# CH335fUSBHub_250914_A.net
KiCad netlist of a schematic drawn in EasyEDA Pro
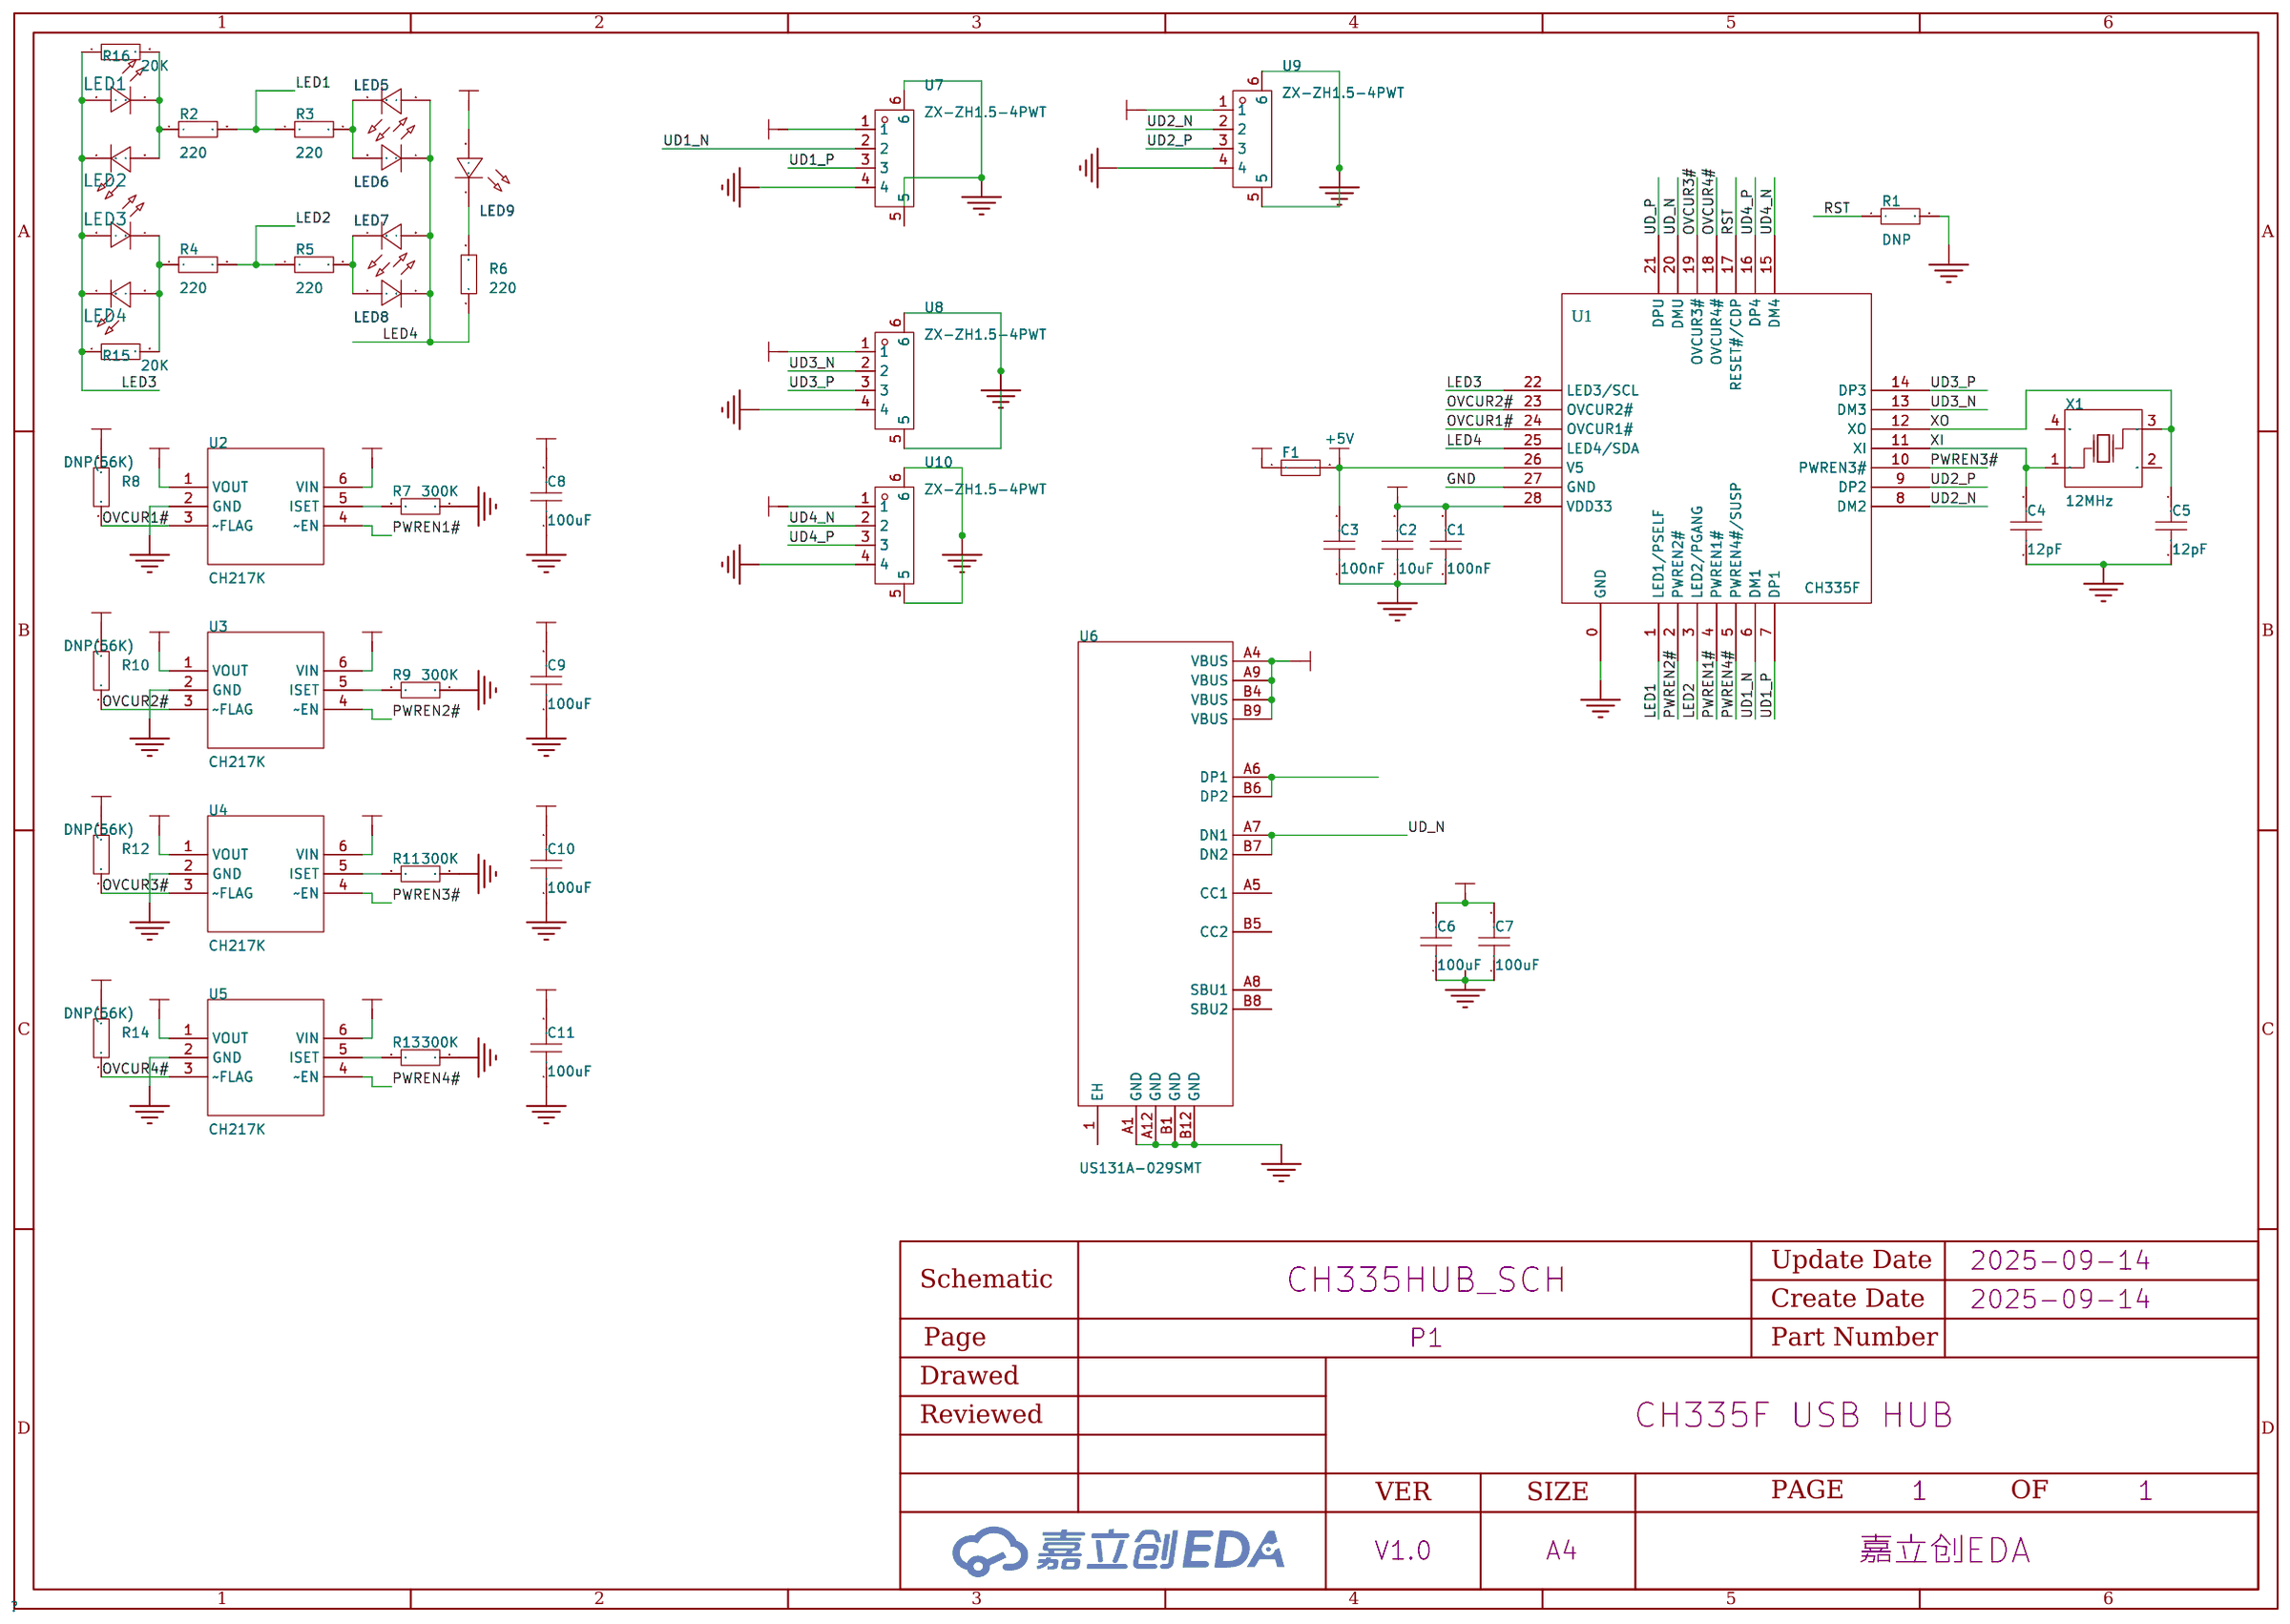
[diagram p0: schematic sheet]

(export (version "E")
  (design (tool "Eeschema 10.0.6"))
  (components
    (comp (ref "C1")
      (value "100nF")
      (footprint "easyedapro:C0805")
      (libsource (lib "easyedapro") (part "CapAcitance"))
    )
    (comp (ref "C2")
      (value "10uF")
      (footprint "easyedapro:C0805")
      (libsource (lib "easyedapro") (part "CapAcitance"))
    )
    (comp (ref "C3")
      (value "100nF")
      (footprint "easyedapro:C0805")
      (libsource (lib "easyedapro") (part "CapAcitance"))
    )
    (comp (ref "C4")
      (value "12pF")
      (footprint "easyedapro:C0805")
      (libsource (lib "easyedapro") (part "CapAcitance"))
    )
    (comp (ref "C5")
      (value "12pF")
      (footprint "easyedapro:C0805")
      (libsource (lib "easyedapro") (part "CapAcitance"))
    )
    (comp (ref "C6")
      (value "100uF")
      (footprint "easyedapro:C0805")
      (libsource (lib "easyedapro") (part "CapAcitance"))
    )
    (comp (ref "C7")
      (value "100uF")
      (footprint "easyedapro:C0805")
      (libsource (lib "easyedapro") (part "CapAcitance"))
    )
    (comp (ref "C8")
      (value "100uF")
      (footprint "easyedapro:C0805")
      (libsource (lib "easyedapro") (part "CapAcitance"))
    )
    (comp (ref "C9")
      (value "100uF")
      (footprint "easyedapro:C0805")
      (libsource (lib "easyedapro") (part "CapAcitance"))
    )
    (comp (ref "C10")
      (value "100uF")
      (footprint "easyedapro:C0805")
      (libsource (lib "easyedapro") (part "CapAcitance"))
    )
    (comp (ref "C11")
      (value "100uF")
      (footprint "easyedapro:C0805")
      (libsource (lib "easyedapro") (part "CapAcitance"))
    )
    (comp (ref "F1")
      (value "SMD0805B050TF")
      (footprint "easyedapro:F0805")
      (description "最大电压:6V;最大电流:100A;保持电流:500mA;跳闸电流:1A;")
      (fields (field (name "Manufacturer") "Brightking(君耀电子)"))
      (libsource (lib "easyedapro") (part "SMD0805B050TF"))
    )
    (comp (ref "LED1")
      (value "~")
      (footprint "easyedapro:LED_0805")
      (libsource (lib "easyedapro") (part "LED_R"))
    )
    (comp (ref "LED2")
      (value "~")
      (footprint "easyedapro:LED_0805")
      (libsource (lib "easyedapro") (part "LED_R"))
    )
    (comp (ref "LED3")
      (value "~")
      (footprint "easyedapro:LED_0805")
      (libsource (lib "easyedapro") (part "LED_R"))
    )
    (comp (ref "LED4")
      (value "~")
      (footprint "easyedapro:LED_0805")
      (libsource (lib "easyedapro") (part "LED_R"))
    )
    (comp (ref "LED5")
      (value "~")
      (footprint "easyedapro:LED_0805")
      (libsource (lib "easyedapro") (part "LED_G"))
    )
    (comp (ref "LED6")
      (value "~")
      (footprint "easyedapro:LED_0805")
      (libsource (lib "easyedapro") (part "LED_G"))
    )
    (comp (ref "LED7")
      (value "~")
      (footprint "easyedapro:LED_0805")
      (libsource (lib "easyedapro") (part "LED_G"))
    )
    (comp (ref "LED8")
      (value "~")
      (footprint "easyedapro:LED_0805")
      (libsource (lib "easyedapro") (part "LED_G"))
    )
    (comp (ref "LED9")
      (value "~")
      (footprint "easyedapro:LED_0805")
      (libsource (lib "easyedapro") (part "LED_G"))
    )
    (comp (ref "R1") (value "DNP") (footprint "easyedapro:R0805") (libsource (lib "easyedapro") (part "电阻")))
    (comp (ref "R2") (value "220") (footprint "easyedapro:R0805") (libsource (lib "easyedapro") (part "电阻")))
    (comp (ref "R3") (value "220") (footprint "easyedapro:R0805") (libsource (lib "easyedapro") (part "电阻")))
    (comp (ref "R4") (value "220") (footprint "easyedapro:R0805") (libsource (lib "easyedapro") (part "电阻")))
    (comp (ref "R5") (value "220") (footprint "easyedapro:R0805") (libsource (lib "easyedapro") (part "电阻")))
    (comp (ref "R6") (value "220") (footprint "easyedapro:R0805") (libsource (lib "easyedapro") (part "电阻")))
    (comp (ref "R7") (value "300K") (footprint "easyedapro:R0805") (libsource (lib "easyedapro") (part "电阻")))
    (comp (ref "R8")
      (value "DNP(56K)")
      (footprint "easyedapro:R0805")
      (libsource (lib "easyedapro") (part "电阻"))
    )
    (comp (ref "R9") (value "300K") (footprint "easyedapro:R0805") (libsource (lib "easyedapro") (part "电阻")))
    (comp (ref "R10")
      (value "DNP(56K)")
      (footprint "easyedapro:R0805")
      (libsource (lib "easyedapro") (part "电阻"))
    )
    (comp (ref "R11")
      (value "300K")
      (footprint "easyedapro:R0805")
      (libsource (lib "easyedapro") (part "电阻"))
    )
    (comp (ref "R12")
      (value "DNP(56K)")
      (footprint "easyedapro:R0805")
      (libsource (lib "easyedapro") (part "电阻"))
    )
    (comp (ref "R13")
      (value "300K")
      (footprint "easyedapro:R0805")
      (libsource (lib "easyedapro") (part "电阻"))
    )
    (comp (ref "R14")
      (value "DNP(56K)")
      (footprint "easyedapro:R0805")
      (libsource (lib "easyedapro") (part "电阻"))
    )
    (comp (ref "R15") (value "20K") (footprint "easyedapro:R0805") (libsource (lib "easyedapro") (part "电阻")))
    (comp (ref "R16") (value "20K") (footprint "easyedapro:R0805") (libsource (lib "easyedapro") (part "电阻")))
    (comp (ref "U1")
      (value "CH335F")
      (footprint "easyedapro:QFN-28_L4.0-W4.0-P0.40-TL")
      (description "4 ports High-Speed USB MTT Hub with 4 over current detect  power control")
      (libsource (lib "easyedapro") (part "CH335F"))
    )
    (comp (ref "U2")
      (value "CH217K")
      (footprint "easyedapro:SOT-23-6_L2.9-W1.6-P0.95-LS2.8-TL")
      (libsource (lib "easyedapro") (part "CH217K"))
    )
    (comp (ref "U3")
      (value "CH217K")
      (footprint "easyedapro:SOT-23-6_L2.9-W1.6-P0.95-LS2.8-TL")
      (libsource (lib "easyedapro") (part "CH217K"))
    )
    (comp (ref "U4")
      (value "CH217K")
      (footprint "easyedapro:SOT-23-6_L2.9-W1.6-P0.95-LS2.8-TL")
      (libsource (lib "easyedapro") (part "CH217K"))
    )
    (comp (ref "U5")
      (value "CH217K")
      (footprint "easyedapro:SOT-23-6_L2.9-W1.6-P0.95-LS2.8-TL")
      (libsource (lib "easyedapro") (part "CH217K"))
    )
    (comp (ref "U6")
      (value "US131A-029SMT")
      (footprint "easyedapro:USB-TYPE-C-SMD_US131A-029SMT")
      (libsource (lib "easyedapro") (part "US131A-029SMT"))
    )
    (comp (ref "U7")
      (value "ZX-ZH1.5-4PWT")
      (footprint "easyedapro:CONN-SMD_4P-P1.50_ZX-ZH1.5-4PWT")
      (fields (field (name "Manufacturer") "Megastar(兆星)"))
      (libsource (lib "easyedapro") (part "ZX-ZH1.5-4PWT"))
    )
    (comp (ref "U8")
      (value "ZX-ZH1.5-4PWT")
      (footprint "easyedapro:CONN-SMD_4P-P1.50_ZX-ZH1.5-4PWT")
      (fields (field (name "Manufacturer") "Megastar(兆星)"))
      (libsource (lib "easyedapro") (part "ZX-ZH1.5-4PWT"))
    )
    (comp (ref "U9")
      (value "ZX-ZH1.5-4PWT")
      (footprint "easyedapro:CONN-SMD_4P-P1.50_ZX-ZH1.5-4PWT")
      (fields (field (name "Manufacturer") "Megastar(兆星)"))
      (libsource (lib "easyedapro") (part "ZX-ZH1.5-4PWT"))
    )
    (comp (ref "U10")
      (value "ZX-ZH1.5-4PWT")
      (footprint "easyedapro:CONN-SMD_4P-P1.50_ZX-ZH1.5-4PWT")
      (fields (field (name "Manufacturer") "Megastar(兆星)"))
      (libsource (lib "easyedapro") (part "ZX-ZH1.5-4PWT"))
    )
    (comp (ref "X1")
      (value "12MHz")
      (footprint "easyedapro:OSC-SMD_4P-L3.2-W2.5-BL")
      (description "频率:12MHz;频率公差:±10ppm;负载电容:20pF;")
      (fields (field (name "Manufacturer Part") "X322512MSB4SI") (field (name "Manufacturer") "YXC(扬兴晶振)"))
      (libsource (lib "easyedapro") (part "X322512MSB4SI"))
    )
  )
  (nets
    (net (code "1") (name "+3.3V") (class "Default")
      (node (ref "C1") (pin "2") (pinfunction "2_2") (pintype "input"))
      (node (ref "C2") (pin "2") (pinfunction "2_2") (pintype "input"))
      (node (ref "LED9") (pin "2") (pinfunction "A_2") (pintype "input"))
      (node (ref "R10") (pin "2") (pinfunction "2_2") (pintype "input"))
      (node (ref "R12") (pin "2") (pinfunction "2_2") (pintype "input"))
      (node (ref "R14") (pin "2") (pinfunction "2_2") (pintype "input"))
      (node (ref "R8") (pin "2") (pinfunction "2_2") (pintype "input"))
      (node (ref "U1") (pin "28") (pinfunction "VDD33_28") (pintype "input"))
    )
    (net (code "2") (name "+5V") (class "Default")
      (node (ref "C3") (pin "2") (pinfunction "2_2") (pintype "input"))
      (node (ref "F1") (pin "2") (pinfunction "2_2") (pintype "input"))
      (node (ref "U1") (pin "26") (pinfunction "V5_26") (pintype "input"))
    )
    (net (code "3") (name "/LED1") (class "Default")
      (node (ref "R2") (pin "2") (pinfunction "2_2") (pintype "input"))
      (node (ref "R3") (pin "1") (pinfunction "1_1") (pintype "input"))
      (node (ref "U1") (pin "1") (pinfunction "LED1/PSELF_1") (pintype "bidirectional"))
    )
    (net (code "4") (name "/LED2") (class "Default")
      (node (ref "R4") (pin "2") (pinfunction "2_2") (pintype "input"))
      (node (ref "R5") (pin "1") (pinfunction "1_1") (pintype "input"))
      (node (ref "U1") (pin "3") (pinfunction "LED2/PGANG_3") (pintype "bidirectional"))
    )
    (net (code "5") (name "/LED3") (class "Default")
      (node (ref "LED1") (pin "2") (pinfunction "A_2") (pintype "input"))
      (node (ref "LED2") (pin "1") (pinfunction "C_1") (pintype "input"))
      (node (ref "LED3") (pin "2") (pinfunction "A_2") (pintype "input"))
      (node (ref "LED4") (pin "1") (pinfunction "C_1") (pintype "input"))
      (node (ref "R15") (pin "1") (pinfunction "1_1") (pintype "input"))
      (node (ref "R16") (pin "1") (pinfunction "1_1") (pintype "input"))
      (node (ref "U1") (pin "22") (pinfunction "LED3/SCL_22") (pintype "bidirectional"))
    )
    (net (code "6") (name "/LED4") (class "Default")
      (node (ref "LED5") (pin "2") (pinfunction "A_2") (pintype "input"))
      (node (ref "LED6") (pin "1") (pinfunction "C_1") (pintype "input"))
      (node (ref "LED7") (pin "2") (pinfunction "A_2") (pintype "input"))
      (node (ref "LED8") (pin "1") (pinfunction "C_1") (pintype "input"))
      (node (ref "R6") (pin "1") (pinfunction "1_1") (pintype "input"))
      (node (ref "U1") (pin "25") (pinfunction "LED4/SDA_25") (pintype "bidirectional"))
    )
    (net (code "7") (name "/OVCUR1#") (class "Default")
      (node (ref "R8") (pin "1") (pinfunction "1_1") (pintype "input"))
      (node (ref "U1") (pin "24") (pinfunction "OVCUR1#_24") (pintype "input"))
      (node (ref "U2") (pin "3") (pinfunction "~FLAG_3") (pintype "input"))
    )
    (net (code "8") (name "/OVCUR2#") (class "Default")
      (node (ref "R10") (pin "1") (pinfunction "1_1") (pintype "input"))
      (node (ref "U1") (pin "23") (pinfunction "OVCUR2#_23") (pintype "input"))
      (node (ref "U3") (pin "3") (pinfunction "~FLAG_3") (pintype "input"))
    )
    (net (code "9") (name "/OVCUR3#") (class "Default")
      (node (ref "R12") (pin "1") (pinfunction "1_1") (pintype "input"))
      (node (ref "U1") (pin "19") (pinfunction "OVCUR3#_19") (pintype "input"))
      (node (ref "U4") (pin "3") (pinfunction "~FLAG_3") (pintype "input"))
    )
    (net (code "10") (name "/OVCUR4#") (class "Default")
      (node (ref "R14") (pin "1") (pinfunction "1_1") (pintype "input"))
      (node (ref "U1") (pin "18") (pinfunction "OVCUR4#_18") (pintype "input"))
      (node (ref "U5") (pin "3") (pinfunction "~FLAG_3") (pintype "input"))
    )
    (net (code "11") (name "/PWREN1#") (class "Default")
      (node (ref "U1") (pin "4") (pinfunction "PWREN1#_4") (pintype "output"))
      (node (ref "U2") (pin "4") (pinfunction "~EN_4") (pintype "input"))
    )
    (net (code "12") (name "/PWREN2#") (class "Default")
      (node (ref "U1") (pin "2") (pinfunction "PWREN2#_2") (pintype "output"))
      (node (ref "U3") (pin "4") (pinfunction "~EN_4") (pintype "input"))
    )
    (net (code "13") (name "/PWREN3#") (class "Default")
      (node (ref "U1") (pin "10") (pinfunction "PWREN3#_10") (pintype "output"))
      (node (ref "U4") (pin "4") (pinfunction "~EN_4") (pintype "input"))
    )
    (net (code "14") (name "/PWREN4#") (class "Default")
      (node (ref "U1") (pin "5") (pinfunction "PWREN4#/SUSP_5") (pintype "output"))
      (node (ref "U5") (pin "4") (pinfunction "~EN_4") (pintype "input"))
    )
    (net (code "15") (name "/RST") (class "Default")
      (node (ref "R1") (pin "1") (pinfunction "1_1") (pintype "input"))
      (node (ref "U1") (pin "17") (pinfunction "RESET#/CDP_17") (pintype "input"))
    )
    (net (code "16") (name "/UD1_N") (class "Default")
      (node (ref "U1") (pin "6") (pinfunction "DM1_6") (pintype "bidirectional"))
      (node (ref "U7") (pin "2") (pinfunction "2_2") (pintype "unspecified"))
    )
    (net (code "17") (name "/UD1_P") (class "Default")
      (node (ref "U1") (pin "7") (pinfunction "DP1_7") (pintype "bidirectional"))
      (node (ref "U7") (pin "3") (pinfunction "3_3") (pintype "unspecified"))
    )
    (net (code "18") (name "/UD2_N") (class "Default")
      (node (ref "U1") (pin "8") (pinfunction "DM2_8") (pintype "bidirectional"))
      (node (ref "U9") (pin "2") (pinfunction "2_2") (pintype "unspecified"))
    )
    (net (code "19") (name "/UD2_P") (class "Default")
      (node (ref "U1") (pin "9") (pinfunction "DP2_9") (pintype "bidirectional"))
      (node (ref "U9") (pin "3") (pinfunction "3_3") (pintype "unspecified"))
    )
    (net (code "20") (name "/UD3_N") (class "Default")
      (node (ref "U1") (pin "13") (pinfunction "DM3_13") (pintype "bidirectional"))
      (node (ref "U8") (pin "2") (pinfunction "2_2") (pintype "unspecified"))
    )
    (net (code "21") (name "/UD3_P") (class "Default")
      (node (ref "U1") (pin "14") (pinfunction "DP3_14") (pintype "bidirectional"))
      (node (ref "U8") (pin "3") (pinfunction "3_3") (pintype "unspecified"))
    )
    (net (code "22") (name "/UD4_N") (class "Default")
      (node (ref "U1") (pin "15") (pinfunction "DM4_15") (pintype "bidirectional"))
      (node (ref "U10") (pin "2") (pinfunction "2_2") (pintype "unspecified"))
    )
    (net (code "23") (name "/UD4_P") (class "Default")
      (node (ref "U1") (pin "16") (pinfunction "DP4_16") (pintype "bidirectional"))
      (node (ref "U10") (pin "3") (pinfunction "3_3") (pintype "unspecified"))
    )
    (net (code "24") (name "/UD_N") (class "Default")
      (node (ref "U1") (pin "20") (pinfunction "DMU_20") (pintype "bidirectional"))
      (node (ref "U6") (pin "A7") (pinfunction "DN1_A7") (pintype "unspecified"))
      (node (ref "U6") (pin "B7") (pinfunction "DN2_B7") (pintype "unspecified"))
    )
    (net (code "25") (name "/UD_P") (class "Default")
      (node (ref "U1") (pin "21") (pinfunction "DPU_21") (pintype "bidirectional"))
    )
    (net (code "26") (name "/XI") (class "Default")
      (node (ref "C4") (pin "2") (pinfunction "2_2") (pintype "input"))
      (node (ref "U1") (pin "11") (pinfunction "XI_11") (pintype "input"))
      (node (ref "X1") (pin "1") (pinfunction "OSC1_1") (pintype "input"))
    )
    (net (code "27") (name "/XO") (class "Default")
      (node (ref "C5") (pin "2") (pinfunction "2_2") (pintype "input"))
      (node (ref "U1") (pin "12") (pinfunction "XO_12") (pintype "output"))
      (node (ref "X1") (pin "3") (pinfunction "OSC2_3") (pintype "input"))
    )
    (net (code "28") (name "GND") (class "Default")
      (node (ref "C1") (pin "1") (pinfunction "1_1") (pintype "input"))
      (node (ref "C10") (pin "1") (pinfunction "1_1") (pintype "input"))
      (node (ref "C11") (pin "1") (pinfunction "1_1") (pintype "input"))
      (node (ref "C2") (pin "1") (pinfunction "1_1") (pintype "input"))
      (node (ref "C3") (pin "1") (pinfunction "1_1") (pintype "input"))
      (node (ref "C4") (pin "1") (pinfunction "1_1") (pintype "input"))
      (node (ref "C5") (pin "1") (pinfunction "1_1") (pintype "input"))
      (node (ref "C6") (pin "1") (pinfunction "1_1") (pintype "input"))
      (node (ref "C7") (pin "1") (pinfunction "1_1") (pintype "input"))
      (node (ref "C8") (pin "1") (pinfunction "1_1") (pintype "input"))
      (node (ref "C9") (pin "1") (pinfunction "1_1") (pintype "input"))
      (node (ref "R1") (pin "2") (pinfunction "2_2") (pintype "input"))
      (node (ref "R11") (pin "1") (pinfunction "1_1") (pintype "input"))
      (node (ref "R13") (pin "1") (pinfunction "1_1") (pintype "input"))
      (node (ref "R7") (pin "1") (pinfunction "1_1") (pintype "input"))
      (node (ref "R9") (pin "1") (pinfunction "1_1") (pintype "input"))
      (node (ref "U1") (pin "0") (pinfunction "GND_0") (pintype "input"))
      (node (ref "U1") (pin "27") (pinfunction "GND_27") (pintype "input"))
      (node (ref "U10") (pin "4") (pinfunction "4_4") (pintype "unspecified"))
      (node (ref "U10") (pin "5") (pinfunction "5_5") (pintype "unspecified"))
      (node (ref "U10") (pin "6") (pinfunction "6_6") (pintype "unspecified"))
      (node (ref "U2") (pin "2") (pinfunction "GND_2") (pintype "input"))
      (node (ref "U3") (pin "2") (pinfunction "GND_2") (pintype "input"))
      (node (ref "U4") (pin "2") (pinfunction "GND_2") (pintype "input"))
      (node (ref "U5") (pin "2") (pinfunction "GND_2") (pintype "input"))
      (node (ref "U6") (pin "A1") (pinfunction "GND_A1") (pintype "unspecified"))
      (node (ref "U6") (pin "A12") (pinfunction "GND_A12") (pintype "unspecified"))
      (node (ref "U6") (pin "B1") (pinfunction "GND_B1") (pintype "unspecified"))
      (node (ref "U6") (pin "B12") (pinfunction "GND_B12") (pintype "unspecified"))
      (node (ref "U7") (pin "4") (pinfunction "4_4") (pintype "unspecified"))
      (node (ref "U7") (pin "5") (pinfunction "5_5") (pintype "unspecified"))
      (node (ref "U7") (pin "6") (pinfunction "6_6") (pintype "unspecified"))
      (node (ref "U8") (pin "4") (pinfunction "4_4") (pintype "unspecified"))
      (node (ref "U8") (pin "5") (pinfunction "5_5") (pintype "unspecified"))
      (node (ref "U8") (pin "6") (pinfunction "6_6") (pintype "unspecified"))
      (node (ref "U9") (pin "4") (pinfunction "4_4") (pintype "unspecified"))
      (node (ref "U9") (pin "5") (pinfunction "5_5") (pintype "unspecified"))
      (node (ref "U9") (pin "6") (pinfunction "6_6") (pintype "unspecified"))
    )
    (net (code "29") (name "Net-(LED1-C)") (class "Default")
      (node (ref "LED1") (pin "1") (pinfunction "C_1") (pintype "input"))
      (node (ref "LED2") (pin "2") (pinfunction "A_2") (pintype "input"))
      (node (ref "R16") (pin "2") (pinfunction "2_2") (pintype "input"))
      (node (ref "R2") (pin "1") (pinfunction "1_1") (pintype "input"))
    )
    (net (code "30") (name "Net-(LED3-C)") (class "Default")
      (node (ref "LED3") (pin "1") (pinfunction "C_1") (pintype "input"))
      (node (ref "LED4") (pin "2") (pinfunction "A_2") (pintype "input"))
      (node (ref "R15") (pin "2") (pinfunction "2_2") (pintype "input"))
      (node (ref "R4") (pin "1") (pinfunction "1_1") (pintype "input"))
    )
    (net (code "31") (name "Net-(LED5-C)") (class "Default")
      (node (ref "LED5") (pin "1") (pinfunction "C_1") (pintype "input"))
      (node (ref "LED6") (pin "2") (pinfunction "A_2") (pintype "input"))
      (node (ref "R3") (pin "2") (pinfunction "2_2") (pintype "input"))
    )
    (net (code "32") (name "Net-(LED7-C)") (class "Default")
      (node (ref "LED7") (pin "1") (pinfunction "C_1") (pintype "input"))
      (node (ref "LED8") (pin "2") (pinfunction "A_2") (pintype "input"))
      (node (ref "R5") (pin "2") (pinfunction "2_2") (pintype "input"))
    )
    (net (code "33") (name "Net-(LED9-C)") (class "Default")
      (node (ref "LED9") (pin "1") (pinfunction "C_1") (pintype "input"))
      (node (ref "R6") (pin "2") (pinfunction "2_2") (pintype "input"))
    )
    (net (code "34") (name "Net-(U2-ISET)") (class "Default")
      (node (ref "R7") (pin "2") (pinfunction "2_2") (pintype "input"))
      (node (ref "U2") (pin "5") (pinfunction "ISET_5") (pintype "input"))
    )
    (net (code "35") (name "Net-(U3-ISET)") (class "Default")
      (node (ref "R9") (pin "2") (pinfunction "2_2") (pintype "input"))
      (node (ref "U3") (pin "5") (pinfunction "ISET_5") (pintype "input"))
    )
    (net (code "36") (name "Net-(U4-ISET)") (class "Default")
      (node (ref "R11") (pin "2") (pinfunction "2_2") (pintype "input"))
      (node (ref "U4") (pin "5") (pinfunction "ISET_5") (pintype "input"))
    )
    (net (code "37") (name "Net-(U5-ISET)") (class "Default")
      (node (ref "R13") (pin "2") (pinfunction "2_2") (pintype "input"))
      (node (ref "U5") (pin "5") (pinfunction "ISET_5") (pintype "input"))
    )
    (net (code "38") (name "Net-(U6-DP1)") (class "Default")
      (node (ref "U6") (pin "A6") (pinfunction "DP1_A6") (pintype "unspecified"))
      (node (ref "U6") (pin "B6") (pinfunction "DP2_B6") (pintype "unspecified"))
    )
    (net (code "39") (name "VIN") (class "Default")
      (node (ref "C6") (pin "2") (pinfunction "2_2") (pintype "input"))
      (node (ref "C7") (pin "2") (pinfunction "2_2") (pintype "input"))
      (node (ref "F1") (pin "1") (pinfunction "1_1") (pintype "input"))
      (node (ref "U2") (pin "6") (pinfunction "VIN_6") (pintype "input"))
      (node (ref "U3") (pin "6") (pinfunction "VIN_6") (pintype "input"))
      (node (ref "U4") (pin "6") (pinfunction "VIN_6") (pintype "input"))
      (node (ref "U5") (pin "6") (pinfunction "VIN_6") (pintype "input"))
      (node (ref "U6") (pin "A4") (pinfunction "VBUS_A4") (pintype "unspecified"))
      (node (ref "U6") (pin "A9") (pinfunction "VBUS_A9") (pintype "unspecified"))
      (node (ref "U6") (pin "B4") (pinfunction "VBUS_B4") (pintype "unspecified"))
      (node (ref "U6") (pin "B9") (pinfunction "VBUS_B9") (pintype "unspecified"))
    )
    (net (code "40") (name "VUSB1") (class "Default")
      (node (ref "C8") (pin "2") (pinfunction "2_2") (pintype "input"))
      (node (ref "U2") (pin "1") (pinfunction "VOUT_1") (pintype "input"))
      (node (ref "U7") (pin "1") (pinfunction "1_1") (pintype "unspecified"))
    )
    (net (code "41") (name "VUSB2") (class "Default")
      (node (ref "C9") (pin "2") (pinfunction "2_2") (pintype "input"))
      (node (ref "U3") (pin "1") (pinfunction "VOUT_1") (pintype "input"))
      (node (ref "U9") (pin "1") (pinfunction "1_1") (pintype "unspecified"))
    )
    (net (code "42") (name "VUSB3") (class "Default")
      (node (ref "C10") (pin "2") (pinfunction "2_2") (pintype "input"))
      (node (ref "U4") (pin "1") (pinfunction "VOUT_1") (pintype "input"))
      (node (ref "U8") (pin "1") (pinfunction "1_1") (pintype "unspecified"))
    )
    (net (code "43") (name "VUSB4") (class "Default")
      (node (ref "C11") (pin "2") (pinfunction "2_2") (pintype "input"))
      (node (ref "U10") (pin "1") (pinfunction "1_1") (pintype "unspecified"))
      (node (ref "U5") (pin "1") (pinfunction "VOUT_1") (pintype "input"))
    )
    (net (code "44") (name "unconnected-(U6-CC1-PadA5)") (class "Default")
      (node (ref "U6") (pin "A5") (pinfunction "CC1_A5") (pintype "unspecified"))
    )
    (net (code "45") (name "unconnected-(U6-CC2-PadB5)") (class "Default")
      (node (ref "U6") (pin "B5") (pinfunction "CC2_B5") (pintype "unspecified"))
    )
    (net (code "46") (name "unconnected-(U6-EH-Pad1)") (class "Default")
      (node (ref "U6") (pin "1") (pinfunction "EH_1") (pintype "unspecified"))
    )
    (net (code "47") (name "unconnected-(U6-SBU1-PadA8)") (class "Default")
      (node (ref "U6") (pin "A8") (pinfunction "SBU1_A8") (pintype "unspecified"))
    )
    (net (code "48") (name "unconnected-(U6-SBU2-PadB8)") (class "Default")
      (node (ref "U6") (pin "B8") (pinfunction "SBU2_B8") (pintype "unspecified"))
    )
    (net (code "49") (name "unconnected-(X1-GND-Pad2)") (class "Default")
      (node (ref "X1") (pin "2") (pinfunction "GND_2") (pintype "input"))
    )
    (net (code "50") (name "unconnected-(X1-GND-Pad4)") (class "Default")
      (node (ref "X1") (pin "4") (pinfunction "GND_4") (pintype "input"))
    )
  )
)
